# Grove_-_Water_Atomization_v1_0.net
KiCad netlist of a schematic drawn in EAGLE
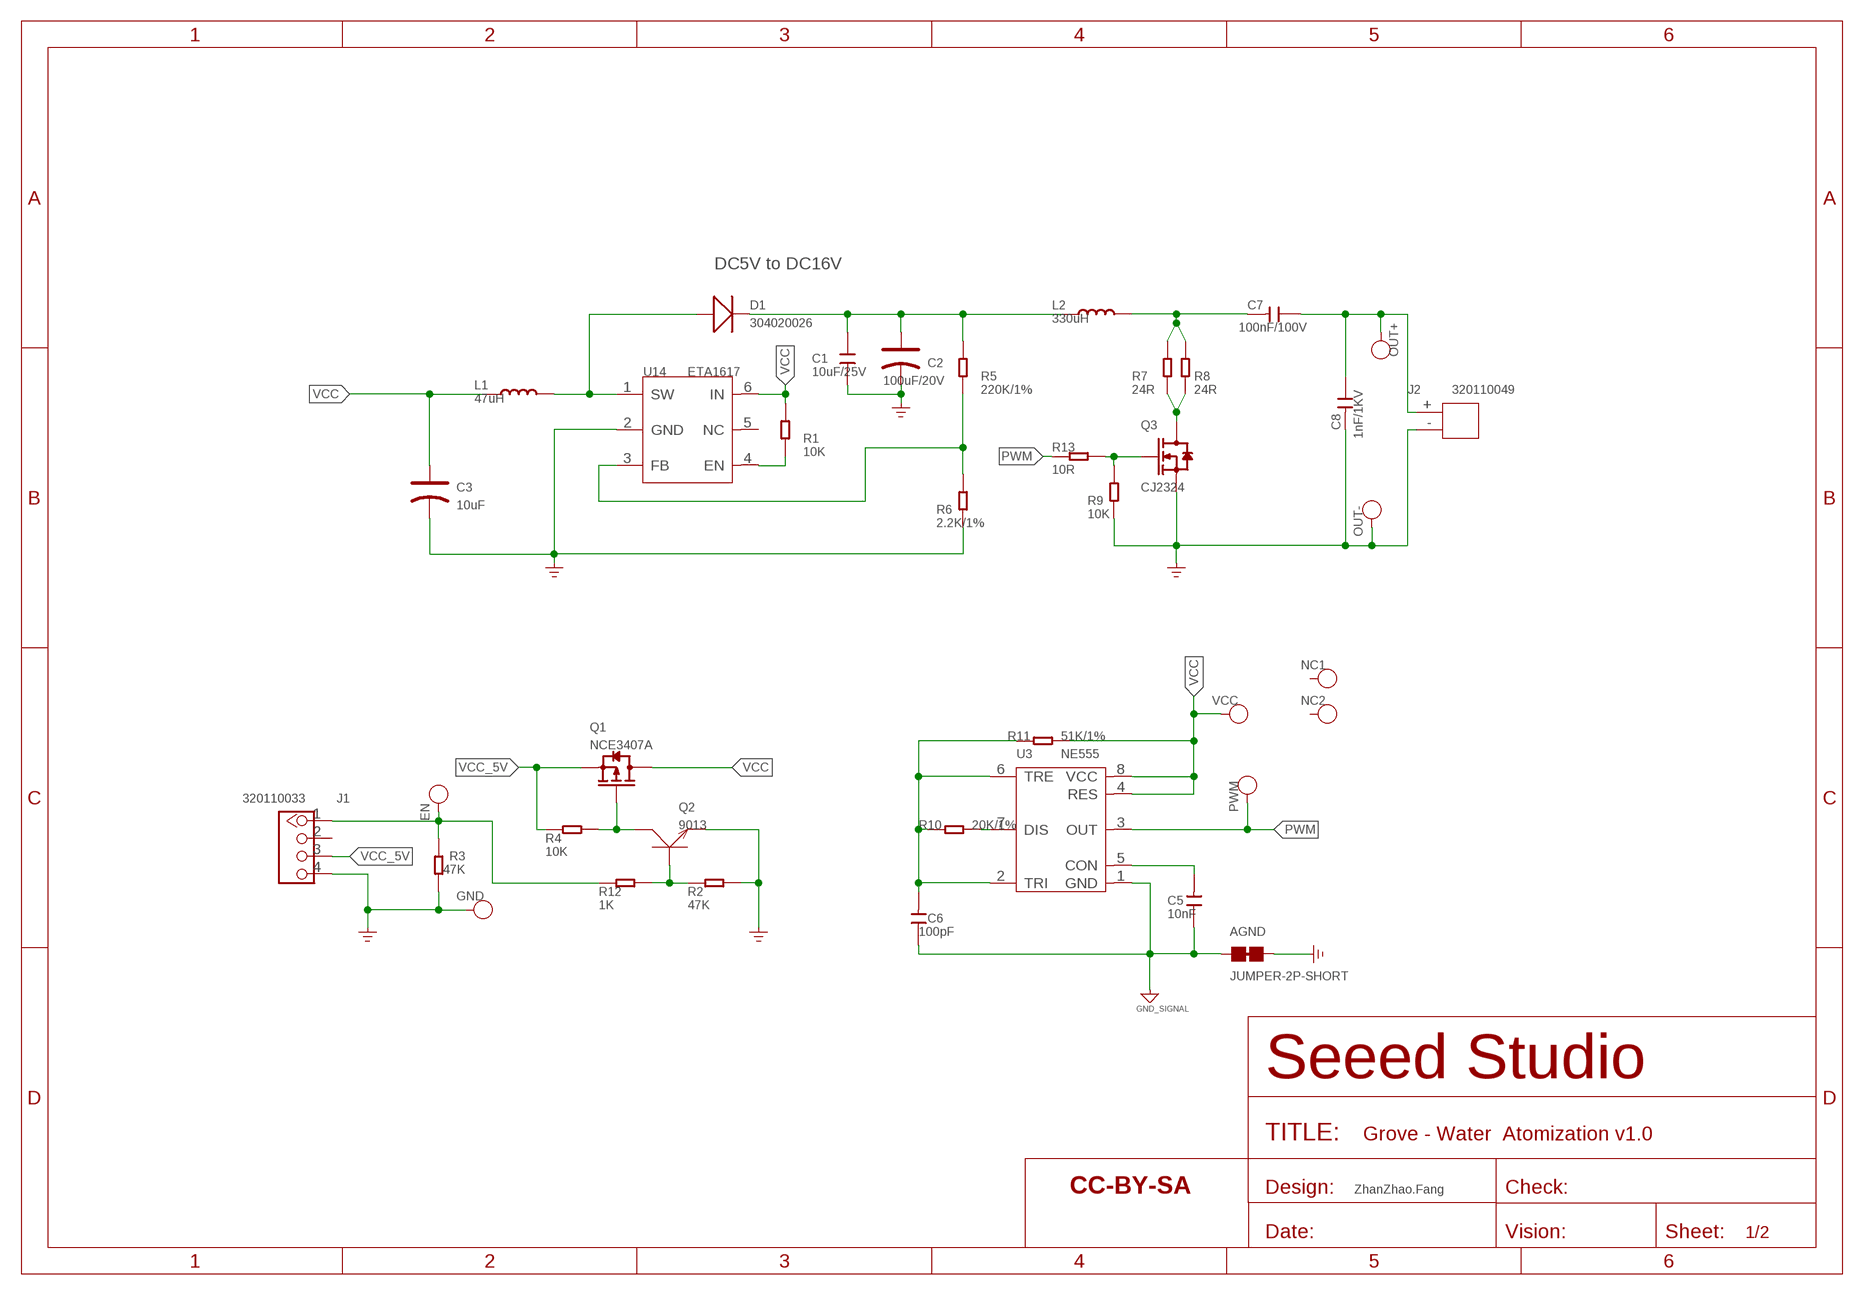
[diagram p0: schematic, sheet 1]

(export (version "E")
  (design (tool "Eeschema 10.0.6"))
  (components
    (comp (ref "AGND")
      (value "JUMPER-2P-SHORT")
      (footprint "eagle-import:2P-SMD-SHORT")
      (libsource (lib "eagle-import") (part "JUMPER-2P-SHORT"))
    )
    (comp (ref "C1")
      (value "10uF/25V")
      (footprint "eagle-import:C1206")
      (libsource (lib "eagle-import") (part "CAP-1206"))
    )
    (comp (ref "C2")
      (value "100uF/20V")
      (footprint "eagle-import:AVX-D")
      (libsource (lib "eagle-import") (part "CAP-POLAR-AVX-D"))
    )
    (comp (ref "C3")
      (value "10uF")
      (footprint "eagle-import:AVX-B")
      (libsource (lib "eagle-import") (part "CAP-POLAR-AVX-B"))
    )
    (comp (ref "C5")
      (value "10nF")
      (footprint "eagle-import:C0402")
      (libsource (lib "eagle-import") (part "CAP-0402"))
    )
    (comp (ref "C6")
      (value "100pF")
      (footprint "eagle-import:C0402")
      (libsource (lib "eagle-import") (part "CAP-0402"))
    )
    (comp (ref "C7")
      (value "100nF/100V")
      (footprint "eagle-import:C0805")
      (libsource (lib "eagle-import") (part "CAP-0805"))
    )
    (comp (ref "C8")
      (value "1nF/1KV")
      (footprint "eagle-import:C1206")
      (libsource (lib "eagle-import") (part "CAP-1206"))
    )
    (comp (ref "D1")
      (value "304020026")
      (footprint "eagle-import:SOD-323")
      (libsource (lib "eagle-import") (part "DIODE'0805'"))
    )
    (comp (ref "EN")
      (value "DNP")
      (footprint "eagle-import:TP-D45MIL")
      (libsource (lib "eagle-import") (part "TEST-POINT'4545'"))
    )
    (comp (ref "GND")
      (value "DNP")
      (footprint "eagle-import:TP-D45MIL")
      (libsource (lib "eagle-import") (part "TEST-POINT'4545'"))
    )
    (comp (ref "J1")
      (value "320110033")
      (footprint "eagle-import:HW4-2.0")
      (libsource (lib "eagle-import") (part "GROVE-CONNECTOR-DIP-2.0"))
    )
    (comp (ref "J2")
      (value "320110049")
      (footprint "eagle-import:H2-2.0-6X4.5MM")
      (libsource (lib "eagle-import") (part "JST-2P-DIP'2.0'"))
    )
    (comp (ref "L1")
      (value "47uH")
      (footprint "eagle-import:INT2-SMD-4.8X4.8X3MM")
      (libsource (lib "eagle-import") (part "INDUCTOR/FERRITE-BEAD"))
    )
    (comp (ref "L2")
      (value "330uH")
      (footprint "eagle-import:INT2-SMD-4.8X4.8X3MM")
      (libsource (lib "eagle-import") (part "INDUCTOR/FERRITE-BEAD"))
    )
    (comp (ref "NC1")
      (value "DNP")
      (footprint "eagle-import:TP-D45MIL")
      (libsource (lib "eagle-import") (part "TEST-POINT'4545'"))
    )
    (comp (ref "NC2")
      (value "DNP")
      (footprint "eagle-import:TP-D45MIL")
      (libsource (lib "eagle-import") (part "TEST-POINT'4545'"))
    )
    (comp (ref "OUT+")
      (value "DNP")
      (footprint "eagle-import:TP-D45MIL")
      (libsource (lib "eagle-import") (part "TEST-POINT'4545'"))
    )
    (comp (ref "OUT-")
      (value "DNP")
      (footprint "eagle-import:TP-D45MIL")
      (libsource (lib "eagle-import") (part "TEST-POINT'4545'"))
    )
    (comp (ref "PWM")
      (value "DNP")
      (footprint "eagle-import:TP-D45MIL")
      (libsource (lib "eagle-import") (part "TEST-POINT'4545'"))
    )
    (comp (ref "Q1")
      (value "NCE3407A")
      (footprint "eagle-import:SOT-23")
      (libsource (lib "eagle-import") (part "MOSFET-P'SI2323CDS/SI2305DS{lt}BR{gt}'"))
    )
    (comp (ref "Q2")
      (value "9013")
      (footprint "eagle-import:SOT-323")
      (libsource (lib "eagle-import") (part "TRANSISTOR-NPN-SOT323"))
    )
    (comp (ref "Q3")
      (value "CJ2324")
      (footprint "eagle-import:SOT-23")
      (libsource (lib "eagle-import") (part "MOSFET-N'SOT23'"))
    )
    (comp (ref "R1")
      (value "10K")
      (footprint "eagle-import:R0402")
      (libsource (lib "eagle-import") (part "RES-0402"))
    )
    (comp (ref "R2")
      (value "47K")
      (footprint "eagle-import:R0402")
      (libsource (lib "eagle-import") (part "RES-0402"))
    )
    (comp (ref "R3")
      (value "47K")
      (footprint "eagle-import:R0402")
      (libsource (lib "eagle-import") (part "RES-0402"))
    )
    (comp (ref "R4")
      (value "10K")
      (footprint "eagle-import:R0402")
      (libsource (lib "eagle-import") (part "RES-0402"))
    )
    (comp (ref "R5")
      (value "220K/1%")
      (footprint "eagle-import:R0402")
      (libsource (lib "eagle-import") (part "RES-0402"))
    )
    (comp (ref "R6")
      (value "2.2K/1%")
      (footprint "eagle-import:R0402")
      (libsource (lib "eagle-import") (part "RES-0402"))
    )
    (comp (ref "R7")
      (value "24R")
      (footprint "eagle-import:R0805")
      (libsource (lib "eagle-import") (part "RES-0805"))
    )
    (comp (ref "R8")
      (value "24R")
      (footprint "eagle-import:R0805")
      (libsource (lib "eagle-import") (part "RES-0805"))
    )
    (comp (ref "R9")
      (value "10K")
      (footprint "eagle-import:R0402")
      (libsource (lib "eagle-import") (part "RES-0402"))
    )
    (comp (ref "R10")
      (value "20K/1%")
      (footprint "eagle-import:R0402")
      (libsource (lib "eagle-import") (part "RES-0402"))
    )
    (comp (ref "R11")
      (value "51K/1%")
      (footprint "eagle-import:R0402")
      (libsource (lib "eagle-import") (part "RES-0402"))
    )
    (comp (ref "R12")
      (value "1K")
      (footprint "eagle-import:R0402")
      (libsource (lib "eagle-import") (part "RES-0402"))
    )
    (comp (ref "R13")
      (value "10R")
      (footprint "eagle-import:R0402")
      (libsource (lib "eagle-import") (part "RES-0402"))
    )
    (comp (ref "U$1")
      (value "DNP")
      (footprint "eagle-import:SEEEDSTUDIO-PCB-FRAME")
      (libsource (lib "eagle-import") (part "SEEEDSTUDIO-OPEN-SCH-FRAME"))
    )
    (comp (ref "U3")
      (value "NE555")
      (footprint "eagle-import:SOIC8-1.27-5X4MM")
      (libsource (lib "eagle-import") (part "CLOCK/TIMING-NE555'DR'"))
    )
    (comp (ref "U14")
      (value "ETA1617")
      (footprint "eagle-import:SOT-23-6")
      (libsource (lib "eagle-import") (part "PMIC-ETA1617"))
    )
    (comp (ref "VCC")
      (value "DNP")
      (footprint "eagle-import:TP-D45MIL")
      (libsource (lib "eagle-import") (part "TEST-POINT'4545'"))
    )
  )
  (nets
    (net (code "1") (name "GND") (class "Default")
      (node (ref "AGND") (pin "2") (pinfunction "2_2") (pintype "bidirectional"))
      (node (ref "C1") (pin "2") (pinfunction "2_2") (pintype "passive"))
      (node (ref "C2") (pin "-") (pinfunction "-_-") (pintype "passive"))
      (node (ref "C3") (pin "-") (pinfunction "-_-") (pintype "passive"))
      (node (ref "C8") (pin "2") (pinfunction "2_2") (pintype "passive"))
      (node (ref "GND") (pin "T") (pinfunction "T_T") (pintype "bidirectional"))
      (node (ref "J1") (pin "4") (pinfunction "4_4") (pintype "bidirectional"))
      (node (ref "J2") (pin "-") (pinfunction "P$2_-") (pintype "bidirectional"))
      (node (ref "OUT-") (pin "T") (pinfunction "T_T") (pintype "bidirectional"))
      (node (ref "Q2") (pin "2") (pinfunction "E_2") (pintype "passive"))
      (node (ref "Q3") (pin "2") (pinfunction "S_2") (pintype "passive"))
      (node (ref "R2") (pin "1") (pinfunction "1_1") (pintype "passive"))
      (node (ref "R3") (pin "2") (pinfunction "2_2") (pintype "passive"))
      (node (ref "R6") (pin "1") (pinfunction "1_1") (pintype "passive"))
      (node (ref "R9") (pin "1") (pinfunction "1_1") (pintype "passive"))
      (node (ref "U14") (pin "2") (pinfunction "GND_2") (pintype "bidirectional"))
    )
    (net (code "2") (name "GND_SIGNAL") (class "Default")
      (node (ref "AGND") (pin "1") (pinfunction "1_1") (pintype "bidirectional"))
      (node (ref "C5") (pin "1") (pinfunction "1_1") (pintype "passive"))
      (node (ref "C6") (pin "1") (pinfunction "1_1") (pintype "passive"))
      (node (ref "U3") (pin "1") (pinfunction "GND_1") (pintype "bidirectional"))
    )
    (net (code "3") (name "Net-(C1-Pad1)") (class "Default")
      (node (ref "C1") (pin "1") (pinfunction "1_1") (pintype "passive"))
      (node (ref "C2") (pin "+") (pinfunction "+_+") (pintype "passive"))
      (node (ref "D1") (pin "-") (pinfunction "-_-") (pintype "passive"))
      (node (ref "L2") (pin "1") (pinfunction "1_1") (pintype "passive"))
      (node (ref "R5") (pin "2") (pinfunction "2_2") (pintype "passive"))
    )
    (net (code "4") (name "Net-(C7-Pad2)") (class "Default")
      (node (ref "C7") (pin "2") (pinfunction "2_2") (pintype "passive"))
      (node (ref "L2") (pin "2") (pinfunction "2_2") (pintype "passive"))
      (node (ref "R7") (pin "2") (pinfunction "2_2") (pintype "passive"))
      (node (ref "R8") (pin "2") (pinfunction "2_2") (pintype "passive"))
    )
    (net (code "5") (name "Net-(EN-PadT)") (class "Default")
      (node (ref "EN") (pin "T") (pinfunction "T_T") (pintype "bidirectional"))
      (node (ref "J1") (pin "1") (pinfunction "1_1") (pintype "bidirectional"))
      (node (ref "R12") (pin "2") (pinfunction "2_2") (pintype "passive"))
      (node (ref "R3") (pin "1") (pinfunction "1_1") (pintype "passive"))
    )
    (net (code "6") (name "Net-(J2-P$1)") (class "Default")
      (node (ref "C7") (pin "1") (pinfunction "1_1") (pintype "passive"))
      (node (ref "C8") (pin "1") (pinfunction "1_1") (pintype "passive"))
      (node (ref "J2") (pin "+") (pinfunction "P$1_+") (pintype "bidirectional"))
      (node (ref "OUT+") (pin "T") (pinfunction "T_T") (pintype "bidirectional"))
    )
    (net (code "7") (name "Net-(Q1-G)") (class "Default")
      (node (ref "Q1") (pin "1") (pinfunction "G_1") (pintype "passive"))
      (node (ref "Q2") (pin "3") (pinfunction "C_3") (pintype "passive"))
      (node (ref "R4") (pin "1") (pinfunction "1_1") (pintype "passive"))
    )
    (net (code "8") (name "Net-(Q2-B)") (class "Default")
      (node (ref "Q2") (pin "1") (pinfunction "B_1") (pintype "passive"))
      (node (ref "R12") (pin "1") (pinfunction "1_1") (pintype "passive"))
      (node (ref "R2") (pin "2") (pinfunction "2_2") (pintype "passive"))
    )
    (net (code "9") (name "Net-(Q3-D)") (class "Default")
      (node (ref "Q3") (pin "3") (pinfunction "D_3") (pintype "passive"))
      (node (ref "R7") (pin "1") (pinfunction "1_1") (pintype "passive"))
      (node (ref "R8") (pin "1") (pinfunction "1_1") (pintype "passive"))
    )
    (net (code "10") (name "Net-(Q3-G)") (class "Default")
      (node (ref "Q3") (pin "1") (pinfunction "G_1") (pintype "passive"))
      (node (ref "R13") (pin "1") (pinfunction "1_1") (pintype "passive"))
      (node (ref "R9") (pin "2") (pinfunction "2_2") (pintype "passive"))
    )
    (net (code "11") (name "Net-(U3-CON)") (class "Default")
      (node (ref "C5") (pin "2") (pinfunction "2_2") (pintype "passive"))
      (node (ref "U3") (pin "5") (pinfunction "CON_5") (pintype "bidirectional"))
    )
    (net (code "12") (name "Net-(U3-DIS)") (class "Default")
      (node (ref "R10") (pin "1") (pinfunction "1_1") (pintype "passive"))
      (node (ref "U3") (pin "7") (pinfunction "DIS_7") (pintype "bidirectional"))
    )
    (net (code "13") (name "Net-(U3-TRE)") (class "Default")
      (node (ref "C6") (pin "2") (pinfunction "2_2") (pintype "passive"))
      (node (ref "R10") (pin "2") (pinfunction "2_2") (pintype "passive"))
      (node (ref "R11") (pin "1") (pinfunction "1_1") (pintype "passive"))
      (node (ref "U3") (pin "2") (pinfunction "TRI_2") (pintype "bidirectional"))
      (node (ref "U3") (pin "6") (pinfunction "TRE_6") (pintype "bidirectional"))
    )
    (net (code "14") (name "Net-(U14-EN)") (class "Default")
      (node (ref "R1") (pin "1") (pinfunction "1_1") (pintype "passive"))
      (node (ref "U14") (pin "4") (pinfunction "EN_4") (pintype "bidirectional"))
    )
    (net (code "15") (name "Net-(U14-FB)") (class "Default")
      (node (ref "R5") (pin "1") (pinfunction "1_1") (pintype "passive"))
      (node (ref "R6") (pin "2") (pinfunction "2_2") (pintype "passive"))
      (node (ref "U14") (pin "3") (pinfunction "FB_3") (pintype "bidirectional"))
    )
    (net (code "16") (name "Net-(U14-SW)") (class "Default")
      (node (ref "D1") (pin "+") (pinfunction "+_+") (pintype "passive"))
      (node (ref "L1") (pin "2") (pinfunction "2_2") (pintype "passive"))
      (node (ref "U14") (pin "1") (pinfunction "SW_1") (pintype "bidirectional"))
    )
    (net (code "17") (name "PWM") (class "Default")
      (node (ref "PWM") (pin "T") (pinfunction "T_T") (pintype "bidirectional"))
      (node (ref "R13") (pin "2") (pinfunction "2_2") (pintype "passive"))
      (node (ref "U3") (pin "3") (pinfunction "OUT_3") (pintype "bidirectional"))
    )
    (net (code "18") (name "VCC") (class "Default")
      (node (ref "C3") (pin "+") (pinfunction "+_+") (pintype "passive"))
      (node (ref "L1") (pin "1") (pinfunction "1_1") (pintype "passive"))
      (node (ref "Q1") (pin "3") (pinfunction "D_3") (pintype "passive"))
      (node (ref "R1") (pin "2") (pinfunction "2_2") (pintype "passive"))
      (node (ref "R11") (pin "2") (pinfunction "2_2") (pintype "passive"))
      (node (ref "U14") (pin "6") (pinfunction "IN_6") (pintype "bidirectional"))
      (node (ref "U3") (pin "4") (pinfunction "RES_4") (pintype "bidirectional"))
      (node (ref "U3") (pin "8") (pinfunction "VCC_8") (pintype "bidirectional"))
      (node (ref "VCC") (pin "T") (pinfunction "T_T") (pintype "bidirectional"))
    )
    (net (code "19") (name "VCC_5V") (class "Default")
      (node (ref "J1") (pin "3") (pinfunction "3_3") (pintype "bidirectional"))
      (node (ref "Q1") (pin "2") (pinfunction "S_2") (pintype "passive"))
      (node (ref "R4") (pin "2") (pinfunction "2_2") (pintype "passive"))
    )
    (net (code "20") (name "unconnected-(J1-Pad2)") (class "Default")
      (node (ref "J1") (pin "2") (pinfunction "2_2") (pintype "bidirectional"))
    )
    (net (code "21") (name "unconnected-(NC1-PadT)") (class "Default")
      (node (ref "NC1") (pin "T") (pinfunction "T_T") (pintype "bidirectional"))
    )
    (net (code "22") (name "unconnected-(NC2-PadT)") (class "Default")
      (node (ref "NC2") (pin "T") (pinfunction "T_T") (pintype "bidirectional"))
    )
    (net (code "23") (name "unconnected-(U14-NC-Pad5)") (class "Default")
      (node (ref "U14") (pin "5") (pinfunction "NC_5") (pintype "bidirectional"))
    )
  )
)
